# Guit2MIDI.net
KiCad netlist of a schematic drawn in EAGLE
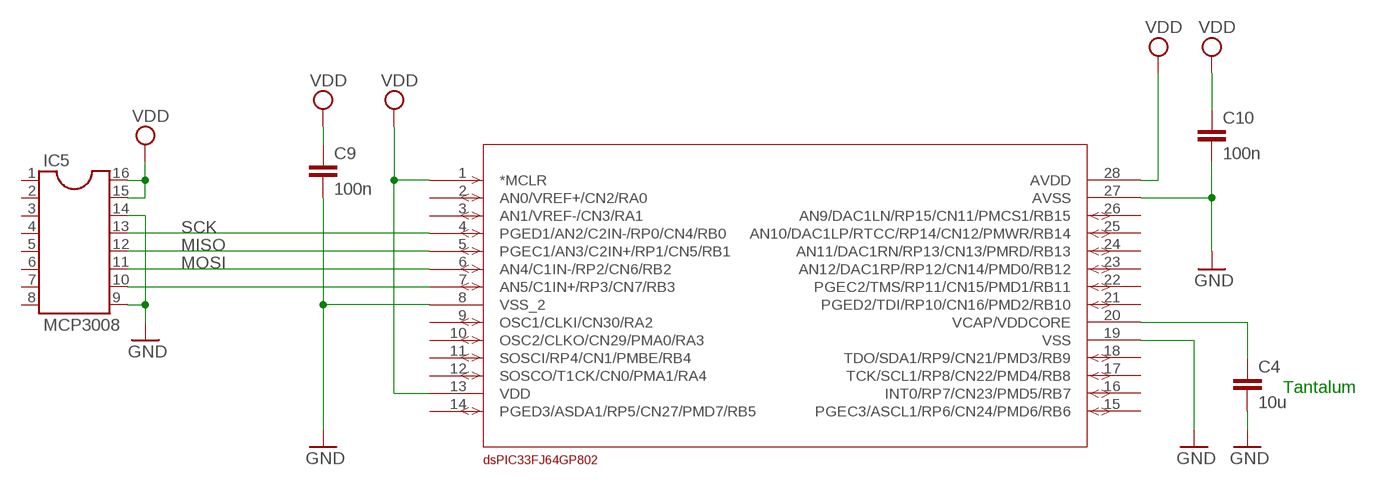
[diagram p0: schematic, sheet 1]

(export (version "E")
  (design (tool "Eeschema 10.0.6"))
  (components
    (comp (ref "C4")
      (value "10u")
      (footprint "eagle-import:C025-030X050")
      (libsource (lib "eagle-import") (part "C-EU025-030X050"))
    )
    (comp (ref "C9")
      (value "100n")
      (footprint "eagle-import:C025-030X050")
      (libsource (lib "eagle-import") (part "C-EU025-030X050"))
    )
    (comp (ref "C10")
      (value "100n")
      (footprint "eagle-import:C025-030X050")
      (libsource (lib "eagle-import") (part "C-EU025-030X050"))
    )
    (comp (ref "IC5")
      (value "MCP3008")
      (footprint "eagle-import:DIL16")
      (libsource (lib "eagle-import") (part "DIL16"))
    )
    (comp (ref "U3")
      (value "DSPIC33FJ64GP802")
      (footprint "eagle-import:SPDIP28_300MC")
      (libsource (lib "eagle-import") (part "DSPIC33FJ64GP802"))
    )
  )
  (nets
    (net (code "1") (name "/MISO") (class "Default")
      (node (ref "IC5") (pin "12") (pinfunction "12_12") (pintype "passive"))
      (node (ref "U3") (pin "5") (pinfunction "PGEC1/AN3/C2IN+/RP1/CN5/RB1_5") (pintype "passive"))
    )
    (net (code "2") (name "/MOSI") (class "Default")
      (node (ref "IC5") (pin "11") (pinfunction "11_11") (pintype "passive"))
      (node (ref "U3") (pin "6") (pinfunction "AN4/C1IN-/RP2/CN6/RB2_6") (pintype "passive"))
    )
    (net (code "3") (name "/SCK") (class "Default")
      (node (ref "IC5") (pin "13") (pinfunction "13_13") (pintype "passive"))
      (node (ref "U3") (pin "4") (pinfunction "PGED1/AN2/C2IN-/RP0/CN4/RB0_4") (pintype "passive"))
    )
    (net (code "4") (name "GND") (class "Default")
      (node (ref "C10") (pin "2") (pinfunction "2_2") (pintype "passive"))
      (node (ref "C4") (pin "2") (pinfunction "2_2") (pintype "passive"))
      (node (ref "C9") (pin "2") (pinfunction "2_2") (pintype "passive"))
      (node (ref "IC5") (pin "14") (pinfunction "14_14") (pintype "passive"))
      (node (ref "IC5") (pin "9") (pinfunction "9_9") (pintype "passive"))
      (node (ref "U3") (pin "19") (pinfunction "VSS_19") (pintype "passive"))
      (node (ref "U3") (pin "27") (pinfunction "AVSS_27") (pintype "passive"))
      (node (ref "U3") (pin "8") (pinfunction "VSS_2_8") (pintype "passive"))
    )
    (net (code "5") (name "Net-(U3-AN5{slash}C1IN+{slash}RP3{slash}CN7{slash}RB3)") (class "Default")
      (node (ref "IC5") (pin "10") (pinfunction "10_10") (pintype "passive"))
      (node (ref "U3") (pin "7") (pinfunction "AN5/C1IN+/RP3/CN7/RB3_7") (pintype "passive"))
    )
    (net (code "6") (name "Net-(U3-VCAP{slash}VDDCORE)") (class "Default")
      (node (ref "C4") (pin "1") (pinfunction "1_1") (pintype "passive"))
      (node (ref "U3") (pin "20") (pinfunction "VCAP/VDDCORE_20") (pintype "passive"))
    )
    (net (code "7") (name "VDD") (class "Default")
      (node (ref "C10") (pin "1") (pinfunction "1_1") (pintype "passive"))
      (node (ref "C9") (pin "1") (pinfunction "1_1") (pintype "passive"))
      (node (ref "IC5") (pin "15") (pinfunction "15_15") (pintype "passive"))
      (node (ref "IC5") (pin "16") (pinfunction "16_16") (pintype "passive"))
      (node (ref "U3") (pin "1") (pinfunction "*MCLR_1") (pintype "passive"))
      (node (ref "U3") (pin "13") (pinfunction "VDD_13") (pintype "passive"))
      (node (ref "U3") (pin "28") (pinfunction "AVDD_28") (pintype "passive"))
    )
    (net (code "8") (name "unconnected-(IC5-Pad1)") (class "Default")
      (node (ref "IC5") (pin "1") (pinfunction "1_1") (pintype "passive"))
    )
    (net (code "9") (name "unconnected-(IC5-Pad2)") (class "Default")
      (node (ref "IC5") (pin "2") (pinfunction "2_2") (pintype "passive"))
    )
    (net (code "10") (name "unconnected-(IC5-Pad3)") (class "Default")
      (node (ref "IC5") (pin "3") (pinfunction "3_3") (pintype "passive"))
    )
    (net (code "11") (name "unconnected-(IC5-Pad4)") (class "Default")
      (node (ref "IC5") (pin "4") (pinfunction "4_4") (pintype "passive"))
    )
    (net (code "12") (name "unconnected-(IC5-Pad5)") (class "Default")
      (node (ref "IC5") (pin "5") (pinfunction "5_5") (pintype "passive"))
    )
    (net (code "13") (name "unconnected-(IC5-Pad6)") (class "Default")
      (node (ref "IC5") (pin "6") (pinfunction "6_6") (pintype "passive"))
    )
    (net (code "14") (name "unconnected-(IC5-Pad7)") (class "Default")
      (node (ref "IC5") (pin "7") (pinfunction "7_7") (pintype "passive"))
    )
    (net (code "15") (name "unconnected-(IC5-Pad8)") (class "Default")
      (node (ref "IC5") (pin "8") (pinfunction "8_8") (pintype "passive"))
    )
    (net (code "16") (name "unconnected-(U3-AN0{slash}VREF+{slash}CN2{slash}RA0-Pad2)") (class "Default")
      (node (ref "U3") (pin "2") (pinfunction "AN0/VREF+/CN2/RA0_2") (pintype "passive"))
    )
    (net (code "17") (name "unconnected-(U3-AN1{slash}VREF-{slash}CN3{slash}RA1-Pad3)") (class "Default")
      (node (ref "U3") (pin "3") (pinfunction "AN1/VREF-/CN3/RA1_3") (pintype "passive"))
    )
    (net (code "18") (name "unconnected-(U3-AN9{slash}DAC1LN{slash}RP15{slash}CN11{slash}PMCS1{slash}RB15-Pad26)") (class "Default")
      (node (ref "U3") (pin "26") (pinfunction "AN9/DAC1LN/RP15/CN11/PMCS1/RB15_26") (pintype "passive"))
    )
    (net (code "19") (name "unconnected-(U3-AN10{slash}DAC1LP{slash}RTCC{slash}RP14{slash}CN12{slash}PMWR{slash}RB14-Pad25)") (class "Default")
      (node (ref "U3") (pin "25") (pinfunction "AN10/DAC1LP/RTCC/RP14/CN12/PMWR/RB14_25") (pintype "passive"))
    )
    (net (code "20") (name "unconnected-(U3-AN11{slash}DAC1RN{slash}RP13{slash}CN13{slash}PMRD{slash}RB13-Pad24)") (class "Default")
      (node (ref "U3") (pin "24") (pinfunction "AN11/DAC1RN/RP13/CN13/PMRD/RB13_24") (pintype "passive"))
    )
    (net (code "21") (name "unconnected-(U3-AN12{slash}DAC1RP{slash}RP12{slash}CN14{slash}PMD0{slash}RB12-Pad23)") (class "Default")
      (node (ref "U3") (pin "23") (pinfunction "AN12/DAC1RP/RP12/CN14/PMD0/RB12_23") (pintype "passive"))
    )
    (net (code "22") (name "unconnected-(U3-INT0{slash}RP7{slash}CN23{slash}PMD5{slash}RB7-Pad16)") (class "Default")
      (node (ref "U3") (pin "16") (pinfunction "INT0/RP7/CN23/PMD5/RB7_16") (pintype "passive"))
    )
    (net (code "23") (name "unconnected-(U3-OSC1{slash}CLKI{slash}CN30{slash}RA2-Pad9)") (class "Default")
      (node (ref "U3") (pin "9") (pinfunction "OSC1/CLKI/CN30/RA2_9") (pintype "passive"))
    )
    (net (code "24") (name "unconnected-(U3-OSC2{slash}CLKO{slash}CN29{slash}PMA0{slash}RA3-Pad10)") (class "Default")
      (node (ref "U3") (pin "10") (pinfunction "OSC2/CLKO/CN29/PMA0/RA3_10") (pintype "passive"))
    )
    (net (code "25") (name "unconnected-(U3-PGEC2{slash}TMS{slash}RP11{slash}CN15{slash}PMD1{slash}RB11-Pad22)") (class "Default")
      (node (ref "U3") (pin "22") (pinfunction "PGEC2/TMS/RP11/CN15/PMD1/RB11_22") (pintype "passive"))
    )
    (net (code "26") (name "unconnected-(U3-PGEC3{slash}ASCL1{slash}RP6{slash}CN24{slash}PMD6{slash}RB6-Pad15)") (class "Default")
      (node (ref "U3") (pin "15") (pinfunction "PGEC3/ASCL1/RP6/CN24/PMD6/RB6_15") (pintype "passive"))
    )
    (net (code "27") (name "unconnected-(U3-PGED2{slash}TDI{slash}RP10{slash}CN16{slash}PMD2{slash}RB10-Pad21)") (class "Default")
      (node (ref "U3") (pin "21") (pinfunction "PGED2/TDI/RP10/CN16/PMD2/RB10_21") (pintype "passive"))
    )
    (net (code "28") (name "unconnected-(U3-PGED3{slash}ASDA1{slash}RP5{slash}CN27{slash}PMD7{slash}RB5-Pad14)") (class "Default")
      (node (ref "U3") (pin "14") (pinfunction "PGED3/ASDA1/RP5/CN27/PMD7/RB5_14") (pintype "passive"))
    )
    (net (code "29") (name "unconnected-(U3-SOSCI{slash}RP4{slash}CN1{slash}PMBE{slash}RB4-Pad11)") (class "Default")
      (node (ref "U3") (pin "11") (pinfunction "SOSCI/RP4/CN1/PMBE/RB4_11") (pintype "passive"))
    )
    (net (code "30") (name "unconnected-(U3-SOSCO{slash}T1CK{slash}CN0{slash}PMA1{slash}RA4-Pad12)") (class "Default")
      (node (ref "U3") (pin "12") (pinfunction "SOSCO/T1CK/CN0/PMA1/RA4_12") (pintype "passive"))
    )
    (net (code "31") (name "unconnected-(U3-TCK{slash}SCL1{slash}RP8{slash}CN22{slash}PMD4{slash}RB8-Pad17)") (class "Default")
      (node (ref "U3") (pin "17") (pinfunction "TCK/SCL1/RP8/CN22/PMD4/RB8_17") (pintype "passive"))
    )
    (net (code "32") (name "unconnected-(U3-TDO{slash}SDA1{slash}RP9{slash}CN21{slash}PMD3{slash}RB9-Pad18)") (class "Default")
      (node (ref "U3") (pin "18") (pinfunction "TDO/SDA1/RP9/CN21/PMD3/RB9_18") (pintype "passive"))
    )
  )
)
